# powersupply5v_ShcDoc.net
KiCad netlist of a schematic drawn in Altium Designer
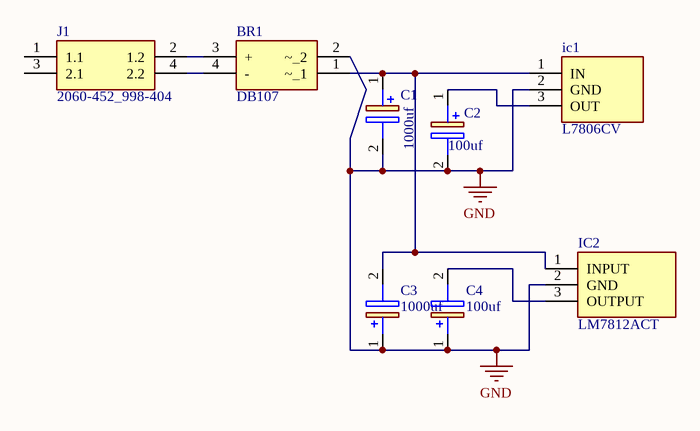
[diagram p0: powersupply5v.ShcDoc.SchDoc]

(export (version "E")
  (design (tool "Eeschema 10.0.6"))
  (components
    (comp (ref "BR1")
      (value "DB107")
      (footprint "SamacSys:DIP825W50P510L830H340Q4N")
      (description "Bridge Rectifier")
      (fields (field (name "MOUSER PART NUMBER") "583-DB107"))
      (libsource (lib "*") (part "DB107"))
    )
    (comp (ref "C1")
      (value "1000uf")
      (footprint "SamacSys:CAPPRD550W60D1050H2150")
      (description "Capacitor Polarised")
      (fields (field (name "MANUFACTURER_PART_NUMBER") "108CKE025M"))
      (libsource (lib "*") (part "108CKE025M"))
    )
    (comp (ref "C2")
      (value "100uf")
      (footprint "SamacSys:CAPPRD500W65D1000H3200")
      (description "Capacitor Polarised")
      (fields
        (field (name "MANUFACTURER_PART_NUMBER") "EEU-FC2A101L")
        (field (name "MOUSER PART NUMBER") "667-EEU-FC2A101L")
      )
      (libsource (lib "*") (part "EEU-FC2A101L"))
    )
    (comp (ref "C3")
      (value "1000uf")
      (footprint "SamacSys:CAPPRD550W60D1050H2150")
      (description "Capacitor Polarised")
      (fields (field (name "MANUFACTURER_PART_NUMBER") "108CKE025M"))
      (libsource (lib "SamacSys") (part "108CKE025M"))
    )
    (comp (ref "C4")
      (value "100uf")
      (footprint "SamacSys:CAPPRD500W65D1000H3200")
      (description "Capacitor Polarised")
      (fields
        (field (name "MANUFACTURER_PART_NUMBER") "EEU-FC2A101L")
        (field (name "MOUSER PART NUMBER") "667-EEU-FC2A101L")
      )
      (libsource (lib "") (part "EEU-FC2A101L_1"))
    )
    (comp (ref "ic1")
      (value "L7806CV")
      (footprint "SamacSys:TO270P460X1020X2008-3P")
      (description "Integrated Circuit")
      (fields (field (name "MOUSER PART NUMBER") "511-L7806CV"))
      (libsource (lib "*") (part "L7806CV"))
    )
    (comp (ref "IC2")
      (value "LM7812ACT")
      (footprint "SamacSys:TO254P470X1016X2019-3P")
      (description "Integrated Circuit")
      (fields (field (name "MOUSER PART NUMBER") "512-LM7812ACT"))
      (libsource (lib "SamacSys") (part "LM7812ACT"))
    )
    (comp (ref "J1")
      (value "2060-452_998-404")
      (footprint "SamacSys:2060452998404")
      (description "Connector")
      (fields (field (name "MANUFACTURER_PART_NUMBER") "2060-452/998-404"))
      (libsource (lib "*") (part "2060-452_998-404"))
    )
  )
  (nets
    (net (code "1") (name "GND") (class "Default")
      (node (ref "BR1") (pin "2") (pinfunction "~_2_2") (pintype "passive"))
      (node (ref "C1") (pin "2") (pinfunction "-_2") (pintype "passive"))
      (node (ref "C2") (pin "2") (pinfunction "-_2") (pintype "passive"))
      (node (ref "C3") (pin "1") (pinfunction "+_1") (pintype "passive"))
      (node (ref "C4") (pin "1") (pinfunction "+_1") (pintype "passive"))
      (node (ref "IC2") (pin "2") (pinfunction "GND_2") (pintype "passive"))
      (node (ref "ic1") (pin "2") (pinfunction "GND_2") (pintype "power_in"))
    )
    (net (code "2") (name "Net-(BR1-+)") (class "Default")
      (node (ref "BR1") (pin "3") (pinfunction "+_3") (pintype "passive"))
      (node (ref "J1") (pin "2") (pinfunction "1.2_2") (pintype "passive"))
    )
    (net (code "3") (name "Net-(BR1--)") (class "Default")
      (node (ref "BR1") (pin "4") (pinfunction "-_4") (pintype "passive"))
      (node (ref "J1") (pin "4") (pinfunction "2.2_4") (pintype "passive"))
    )
    (net (code "4") (name "Net-(BR1-~_1)") (class "Default")
      (node (ref "BR1") (pin "1") (pinfunction "~_1_1") (pintype "passive"))
      (node (ref "C1") (pin "1") (pinfunction "+_1") (pintype "passive"))
      (node (ref "C3") (pin "2") (pinfunction "-_2") (pintype "passive"))
      (node (ref "IC2") (pin "1") (pinfunction "INPUT_1") (pintype "passive"))
      (node (ref "ic1") (pin "1") (pinfunction "IN_1") (pintype "power_in"))
    )
    (net (code "5") (name "Net-(C2-+)") (class "Default")
      (node (ref "C2") (pin "1") (pinfunction "+_1") (pintype "passive"))
      (node (ref "ic1") (pin "3") (pinfunction "OUT_3") (pintype "power_in"))
    )
    (net (code "6") (name "Net-(C4--)") (class "Default")
      (node (ref "C4") (pin "2") (pinfunction "-_2") (pintype "passive"))
      (node (ref "IC2") (pin "3") (pinfunction "OUTPUT_3") (pintype "passive"))
    )
    (net (code "7") (name "unconnected-(J1-1.1-Pad1)") (class "Default")
      (node (ref "J1") (pin "1") (pinfunction "1.1_1") (pintype "passive"))
    )
    (net (code "8") (name "unconnected-(J1-2.1-Pad3)") (class "Default")
      (node (ref "J1") (pin "3") (pinfunction "2.1_3") (pintype "passive"))
    )
  )
)
